# Mainboard_User_Interface.net
KiCad netlist of a schematic drawn in Altium Designer
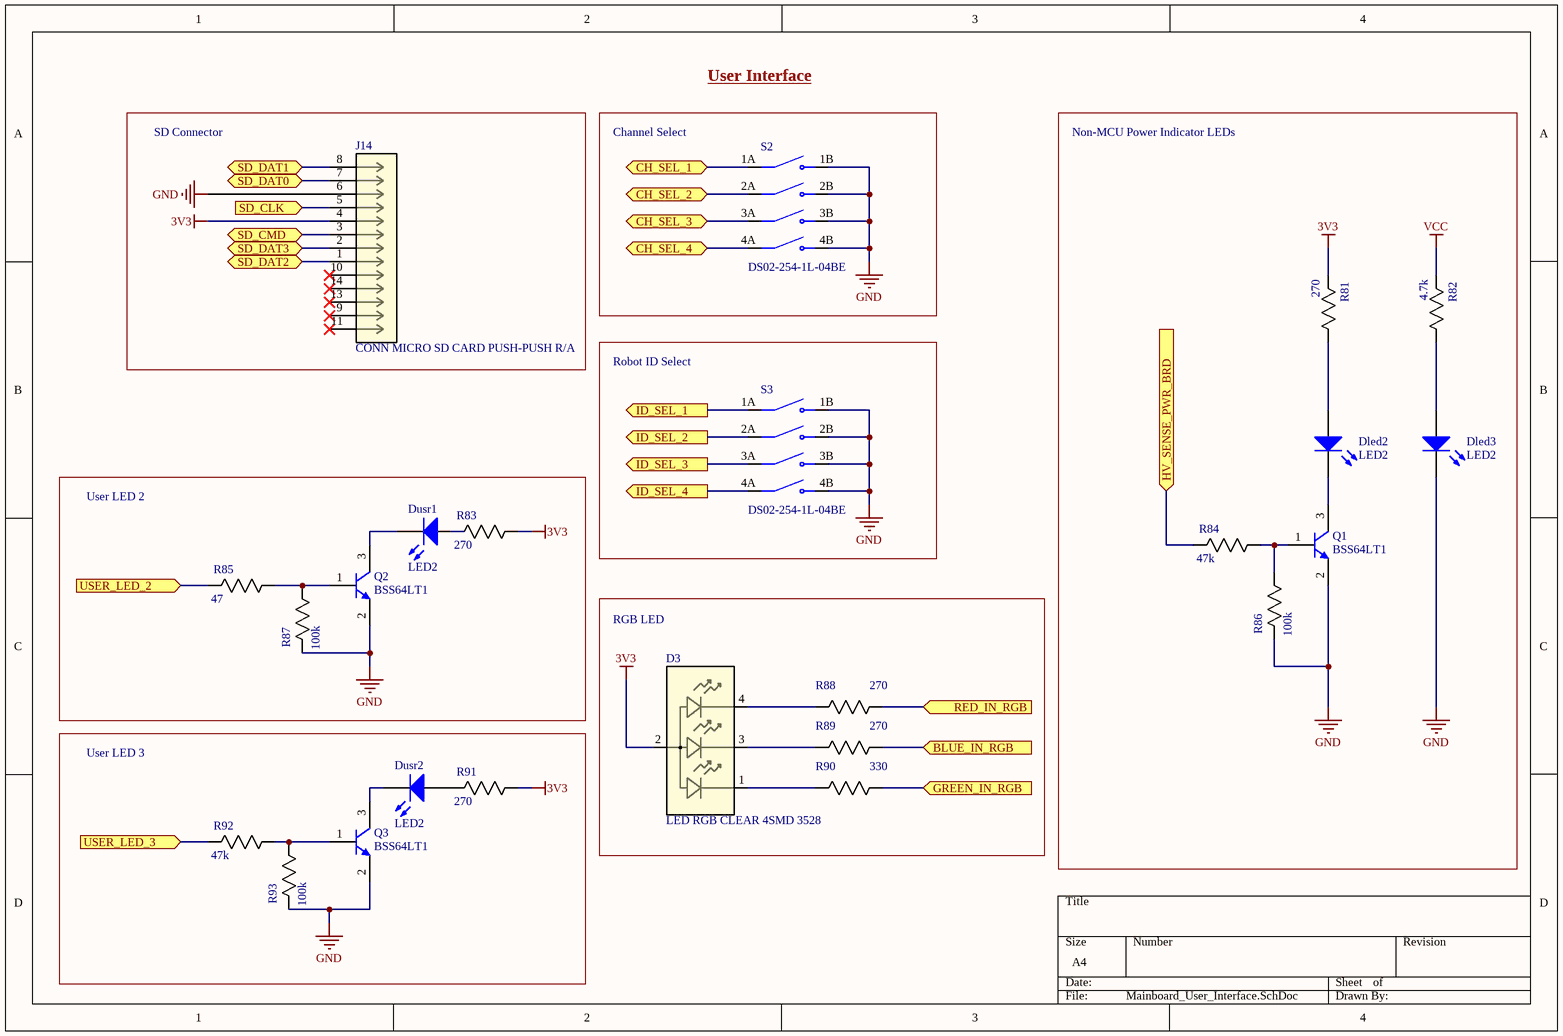
[diagram p0: Mainboard_User_Interface.SchDoc]

(export (version "E")
  (design (tool "Eeschema 10.0.6"))
  (components
    (comp (ref "D3")
      (value "LED RGB CLEAR 4SMD 3528")
      (footprint "LED 4pin 3.5 x 2.8")
      (description "LED RGB No Lead \r\nAAA3528")
      (libsource (lib "AltiumLibraries") (part "LED RGB CLEAR 4SMD 3528"))
    )
    (comp (ref "Dled2")
      (value "LED2")
      (footprint "3.2X1.6X1.1")
      (description "Typical RED, GREEN, YELLOW, AMBER GaAs LED")
      (libsource (lib "AltiumLibraries") (part "LED GREEN SMD"))
    )
    (comp (ref "Dled3")
      (value "LED2")
      (footprint "3.2X1.6X1.1")
      (description "Typical RED, GREEN, YELLOW, AMBER GaAs LED")
      (libsource (lib "AltiumLibraries") (part "LED GREEN SMD"))
    )
    (comp (ref "Dusr1")
      (value "LED2")
      (footprint "3.2X1.6X1.1")
      (description "Typical RED, GREEN, YELLOW, AMBER GaAs LED")
      (libsource (lib "AltiumLibraries") (part "LED GREEN SMD"))
    )
    (comp (ref "Dusr2")
      (value "LED2")
      (footprint "3.2X1.6X1.1")
      (description "Typical RED, GREEN, YELLOW, AMBER GaAs LED")
      (libsource (lib "AltiumLibraries") (part "LED RED SMD"))
    )
    (comp (ref "J14")
      (value "CONN MICRO SD CARD PUSH-PUSH R/A")
      (footprint "SD Connector 5027740891")
      (description "10 (8 + 2) Position Card Connector Secure Digital - microSD™ Surface Mount, Right Angle Gold")
      (fields (field (name "MF") "Molex") (field (name "MP") "5027740891"))
      (libsource (lib "AltiumLibraries") (part "CONN MICRO SD CARD PUSH-PUSH R/A"))
    )
    (comp (ref "Q1")
      (value "BSS64LT1")
      (footprint "ONSC-SOT-23-3-318-08_V")
      (description "Driver Transistor, NPN Silicon, 3-Pin SOT-23, Tape and Reel")
      (fields (field (name "MANUFACTURER") "On Semiconductor"))
      (libsource (lib "Altium Content Vault") (part "ONSC-NPN-B1E2C3-3"))
    )
    (comp (ref "Q2")
      (value "BSS64LT1")
      (footprint "ONSC-SOT-23-3-318-08_V")
      (description "Driver Transistor, NPN Silicon, 3-Pin SOT-23, Tape and Reel")
      (fields (field (name "MANUFACTURER") "On Semiconductor"))
      (libsource (lib "Altium Content Vault") (part "ONSC-NPN-B1E2C3-3"))
    )
    (comp (ref "Q3")
      (value "BSS64LT1")
      (footprint "ONSC-SOT-23-3-318-08_V")
      (description "Driver Transistor, NPN Silicon, 3-Pin SOT-23, Tape and Reel")
      (fields (field (name "MANUFACTURER") "On Semiconductor"))
      (libsource (lib "Altium Content Vault") (part "ONSC-NPN-B1E2C3-3"))
    )
    (comp (ref "R81")
      (value "270")
      (footprint "0805")
      (description "RES SMD 270 OHM 5% 1/8W 0805")
      (fields (field (name "TOLERANCE") "5%"))
      (libsource (lib "AltiumLibraries") (part "RES 270.0 1/8W"))
    )
    (comp (ref "R82")
      (value "4.7k")
      (footprint "0805")
      (description "RES SMD 4.7k OHM 5% 1/8W 0805")
      (fields (field (name "TOLERANCE") "5%"))
      (libsource (lib "AltiumLibraries") (part "RES 4.7k 1/8W - 5%"))
    )
    (comp (ref "R83")
      (value "270")
      (footprint "0805")
      (description "RES SMD 270 OHM 5% 1/8W 0805")
      (fields (field (name "TOLERANCE") "5%"))
      (libsource (lib "") (part "RES 270.0 1/8W_1"))
    )
    (comp (ref "R84")
      (value "47k")
      (footprint "0805")
      (description "RES SMD 47K OHM 1% 1/8W 0805")
      (fields (field (name "TOLERANCE") "1%"))
      (libsource (lib "AltiumLibraries") (part "RES 47k 1/8W - 1%"))
    )
    (comp (ref "R85")
      (value "47")
      (footprint "0805")
      (description "RES SMD 47 OHM 1% 1/8W 0805")
      (fields (field (name "TOLERANCE") "1%"))
      (libsource (lib "AltiumLibraries") (part "RES 47.0 1/8W - 1%"))
    )
    (comp (ref "R86")
      (value "100k")
      (footprint "0805")
      (description "RES SMD 100K OHM 1% 1/8W 0805")
      (fields (field (name "TOLERANCE") "1%"))
      (libsource (lib "AltiumLibraries") (part "RES 100k 1/8W - 1%"))
    )
    (comp (ref "R87")
      (value "100k")
      (footprint "0805")
      (description "RES SMD 100K OHM 1% 1/8W 0805")
      (fields (field (name "TOLERANCE") "1%"))
      (libsource (lib "") (part "RES 100k 1/8W - 1%_1"))
    )
    (comp (ref "R88")
      (value "270")
      (footprint "0805")
      (description "RES SMD 270 OHM 5% 1/8W 0805")
      (fields (field (name "TOLERANCE") "5%"))
      (libsource (lib "AltiumLibraries") (part "RES 270.0 1/8W"))
    )
    (comp (ref "R89")
      (value "270")
      (footprint "0805")
      (description "RES SMD 270 OHM 5% 1/8W 0805")
      (fields (field (name "TOLERANCE") "5%"))
      (libsource (lib "AltiumLibraries") (part "RES 270.0 1/8W"))
    )
    (comp (ref "R90")
      (value "330")
      (footprint "0805")
      (description "RES SMD 330 OHM 1% 1/8W 0805")
      (fields (field (name "TOLERANCE") "1%"))
      (libsource (lib "AltiumLibraries") (part "RES 330.0 1/8W - 1%"))
    )
    (comp (ref "R91")
      (value "270")
      (footprint "0805")
      (description "RES SMD 270 OHM 5% 1/8W 0805")
      (fields (field (name "TOLERANCE") "5%"))
      (libsource (lib "") (part "RES 270.0 1/8W_1"))
    )
    (comp (ref "R92")
      (value "47k")
      (footprint "0805")
      (description "RES SMD 47K OHM 1% 1/8W 0805")
      (fields (field (name "TOLERANCE") "1%"))
      (libsource (lib "AltiumLibraries") (part "RES 47k 1/8W - 1%"))
    )
    (comp (ref "R93")
      (value "100k")
      (footprint "0805")
      (description "RES SMD 100K OHM 1% 1/8W 0805")
      (fields (field (name "TOLERANCE") "1%"))
      (libsource (lib "") (part "RES 100k 1/8W - 1%_1"))
    )
    (comp (ref "S2")
      (value "DS02-254-1L-04BE")
      (footprint "SW_DS02-254-1L-04BE")
      (description "Dip Switch Piano Key 4-position")
      (libsource (lib "AltiumLibraries") (part "DS02-254-1L-04BE"))
    )
    (comp (ref "S3")
      (value "DS02-254-1L-04BE")
      (footprint "SW_DS02-254-1L-04BE")
      (description "Dip Switch Piano Key 4-position")
      (libsource (lib "AltiumLibraries") (part "DS02-254-1L-04BE"))
    )
  )
  (nets
    (net (code "1") (name "/BLUE_IN_RGB") (class "Default")
      (node (ref "R89") (pin "1") (pinfunction "R1_1") (pintype "passive"))
    )
    (net (code "2") (name "/CH_SEL_1") (class "Default")
      (node (ref "S2") (pin "1A") (pinfunction "COM1_1A") (pintype "passive"))
    )
    (net (code "3") (name "/CH_SEL_2") (class "Default")
      (node (ref "S2") (pin "2A") (pinfunction "COM2_2A") (pintype "passive"))
    )
    (net (code "4") (name "/CH_SEL_3") (class "Default")
      (node (ref "S2") (pin "3A") (pinfunction "COM3_3A") (pintype "passive"))
    )
    (net (code "5") (name "/CH_SEL_4") (class "Default")
      (node (ref "S2") (pin "4A") (pinfunction "COM4_4A") (pintype "passive"))
    )
    (net (code "6") (name "/GREEN_IN_RGB") (class "Default")
      (node (ref "R90") (pin "1") (pinfunction "R1_1") (pintype "passive"))
    )
    (net (code "7") (name "/HV_SENSE_PWR_BRD") (class "Default")
      (node (ref "R84") (pin "2") (pinfunction "R2_2") (pintype "passive"))
    )
    (net (code "8") (name "/ID_SEL_1") (class "Default")
      (node (ref "S3") (pin "1A") (pinfunction "COM1_1A") (pintype "passive"))
    )
    (net (code "9") (name "/ID_SEL_2") (class "Default")
      (node (ref "S3") (pin "2A") (pinfunction "COM2_2A") (pintype "passive"))
    )
    (net (code "10") (name "/ID_SEL_3") (class "Default")
      (node (ref "S3") (pin "3A") (pinfunction "COM3_3A") (pintype "passive"))
    )
    (net (code "11") (name "/ID_SEL_4") (class "Default")
      (node (ref "S3") (pin "4A") (pinfunction "COM4_4A") (pintype "passive"))
    )
    (net (code "12") (name "/RED_IN_RGB") (class "Default")
      (node (ref "R88") (pin "1") (pinfunction "R1_1") (pintype "passive"))
    )
    (net (code "13") (name "/SD_CLK") (class "Default")
      (node (ref "J14") (pin "5") (pinfunction "5_5") (pintype "passive"))
    )
    (net (code "14") (name "/SD_CMD") (class "Default")
      (node (ref "J14") (pin "3") (pinfunction "3_3") (pintype "passive"))
    )
    (net (code "15") (name "/SD_DAT0") (class "Default")
      (node (ref "J14") (pin "7") (pinfunction "7_7") (pintype "passive"))
    )
    (net (code "16") (name "/SD_DAT1") (class "Default")
      (node (ref "J14") (pin "8") (pinfunction "8_8") (pintype "passive"))
    )
    (net (code "17") (name "/SD_DAT2") (class "Default")
      (node (ref "J14") (pin "1") (pinfunction "1_1") (pintype "passive"))
    )
    (net (code "18") (name "/SD_DAT3") (class "Default")
      (node (ref "J14") (pin "2") (pinfunction "2_2") (pintype "passive"))
    )
    (net (code "19") (name "/USER_LED_2") (class "Default")
      (node (ref "R85") (pin "2") (pinfunction "R2_2") (pintype "passive"))
    )
    (net (code "20") (name "/USER_LED_3") (class "Default")
      (node (ref "R92") (pin "2") (pinfunction "R2_2") (pintype "passive"))
    )
    (net (code "21") (name "3V3") (class "Default")
      (node (ref "D3") (pin "2") (pinfunction "2_2") (pintype "passive"))
      (node (ref "J14") (pin "4") (pinfunction "4_4") (pintype "passive"))
      (node (ref "R81") (pin "2") (pinfunction "R2_2") (pintype "passive"))
      (node (ref "R83") (pin "1") (pinfunction "R1_1") (pintype "passive"))
      (node (ref "R91") (pin "1") (pinfunction "R1_1") (pintype "passive"))
    )
    (net (code "22") (name "GND") (class "Default")
      (node (ref "Dled3") (pin "2") (pinfunction "K_2") (pintype "passive"))
      (node (ref "J14") (pin "6") (pinfunction "6_6") (pintype "passive"))
      (node (ref "Q1") (pin "2") (pinfunction "E_2") (pintype "passive"))
      (node (ref "Q2") (pin "2") (pinfunction "E_2") (pintype "passive"))
      (node (ref "Q3") (pin "2") (pinfunction "E_2") (pintype "passive"))
      (node (ref "R86") (pin "2") (pinfunction "R2_2") (pintype "passive"))
      (node (ref "R87") (pin "2") (pinfunction "R2_2") (pintype "passive"))
      (node (ref "R93") (pin "2") (pinfunction "R2_2") (pintype "passive"))
      (node (ref "S2") (pin "1B") (pinfunction "NO1_1B") (pintype "passive"))
      (node (ref "S2") (pin "2B") (pinfunction "NO2_2B") (pintype "passive"))
      (node (ref "S2") (pin "3B") (pinfunction "NO3_3B") (pintype "passive"))
      (node (ref "S2") (pin "4B") (pinfunction "NO4_4B") (pintype "passive"))
      (node (ref "S3") (pin "1B") (pinfunction "NO1_1B") (pintype "passive"))
      (node (ref "S3") (pin "2B") (pinfunction "NO2_2B") (pintype "passive"))
      (node (ref "S3") (pin "3B") (pinfunction "NO3_3B") (pintype "passive"))
      (node (ref "S3") (pin "4B") (pinfunction "NO4_4B") (pintype "passive"))
    )
    (net (code "23") (name "Net-(Dled2-A)") (class "Default")
      (node (ref "Dled2") (pin "1") (pinfunction "A_1") (pintype "passive"))
      (node (ref "R81") (pin "1") (pinfunction "R1_1") (pintype "passive"))
    )
    (net (code "24") (name "Net-(Dled2-K)") (class "Default")
      (node (ref "Dled2") (pin "2") (pinfunction "K_2") (pintype "passive"))
      (node (ref "Q1") (pin "3") (pinfunction "C_3") (pintype "passive"))
    )
    (net (code "25") (name "Net-(Dled3-A)") (class "Default")
      (node (ref "Dled3") (pin "1") (pinfunction "A_1") (pintype "passive"))
      (node (ref "R82") (pin "1") (pinfunction "R1_1") (pintype "passive"))
    )
    (net (code "26") (name "Net-(Dusr1-A)") (class "Default")
      (node (ref "Dusr1") (pin "1") (pinfunction "A_1") (pintype "passive"))
      (node (ref "R83") (pin "2") (pinfunction "R2_2") (pintype "passive"))
    )
    (net (code "27") (name "Net-(Dusr1-K)") (class "Default")
      (node (ref "Dusr1") (pin "2") (pinfunction "K_2") (pintype "passive"))
      (node (ref "Q2") (pin "3") (pinfunction "C_3") (pintype "passive"))
    )
    (net (code "28") (name "Net-(Dusr2-A)") (class "Default")
      (node (ref "Dusr2") (pin "1") (pinfunction "A_1") (pintype "passive"))
      (node (ref "R91") (pin "2") (pinfunction "R2_2") (pintype "passive"))
    )
    (net (code "29") (name "Net-(Dusr2-K)") (class "Default")
      (node (ref "Dusr2") (pin "2") (pinfunction "K_2") (pintype "passive"))
      (node (ref "Q3") (pin "3") (pinfunction "C_3") (pintype "passive"))
    )
    (net (code "30") (name "Net-(Q1-B)") (class "Default")
      (node (ref "Q1") (pin "1") (pinfunction "B_1") (pintype "passive"))
      (node (ref "R84") (pin "1") (pinfunction "R1_1") (pintype "passive"))
      (node (ref "R86") (pin "1") (pinfunction "R1_1") (pintype "passive"))
    )
    (net (code "31") (name "Net-(Q2-B)") (class "Default")
      (node (ref "Q2") (pin "1") (pinfunction "B_1") (pintype "passive"))
      (node (ref "R85") (pin "1") (pinfunction "R1_1") (pintype "passive"))
      (node (ref "R87") (pin "1") (pinfunction "R1_1") (pintype "passive"))
    )
    (net (code "32") (name "Net-(Q3-B)") (class "Default")
      (node (ref "Q3") (pin "1") (pinfunction "B_1") (pintype "passive"))
      (node (ref "R92") (pin "1") (pinfunction "R1_1") (pintype "passive"))
      (node (ref "R93") (pin "1") (pinfunction "R1_1") (pintype "passive"))
    )
    (net (code "33") (name "Net-(R88-R2)") (class "Default")
      (node (ref "D3") (pin "4") (pinfunction "4_4") (pintype "passive"))
      (node (ref "R88") (pin "2") (pinfunction "R2_2") (pintype "passive"))
    )
    (net (code "34") (name "Net-(R89-R2)") (class "Default")
      (node (ref "D3") (pin "3") (pinfunction "3_3") (pintype "passive"))
      (node (ref "R89") (pin "2") (pinfunction "R2_2") (pintype "passive"))
    )
    (net (code "35") (name "Net-(R90-R2)") (class "Default")
      (node (ref "D3") (pin "1") (pinfunction "1_1") (pintype "passive"))
      (node (ref "R90") (pin "2") (pinfunction "R2_2") (pintype "passive"))
    )
    (net (code "36") (name "VCC") (class "Default")
      (node (ref "R82") (pin "2") (pinfunction "R2_2") (pintype "passive"))
    )
    (net (code "37") (name "unconnected-(J14-Pad9)") (class "Default")
      (node (ref "J14") (pin "9") (pinfunction "9_9") (pintype "passive+no_connect"))
    )
    (net (code "38") (name "unconnected-(J14-Pad10)") (class "Default")
      (node (ref "J14") (pin "10") (pinfunction "10_10") (pintype "passive+no_connect"))
    )
    (net (code "39") (name "unconnected-(J14-Pad11)") (class "Default")
      (node (ref "J14") (pin "11") (pinfunction "11_11") (pintype "passive+no_connect"))
    )
    (net (code "40") (name "unconnected-(J14-Pad13)") (class "Default")
      (node (ref "J14") (pin "13") (pinfunction "13_13") (pintype "passive+no_connect"))
    )
    (net (code "41") (name "unconnected-(J14-Pad14)") (class "Default")
      (node (ref "J14") (pin "14") (pinfunction "14_14") (pintype "passive+no_connect"))
    )
  )
)
